# mcu.net
KiCad netlist of a schematic drawn in Altium Designer
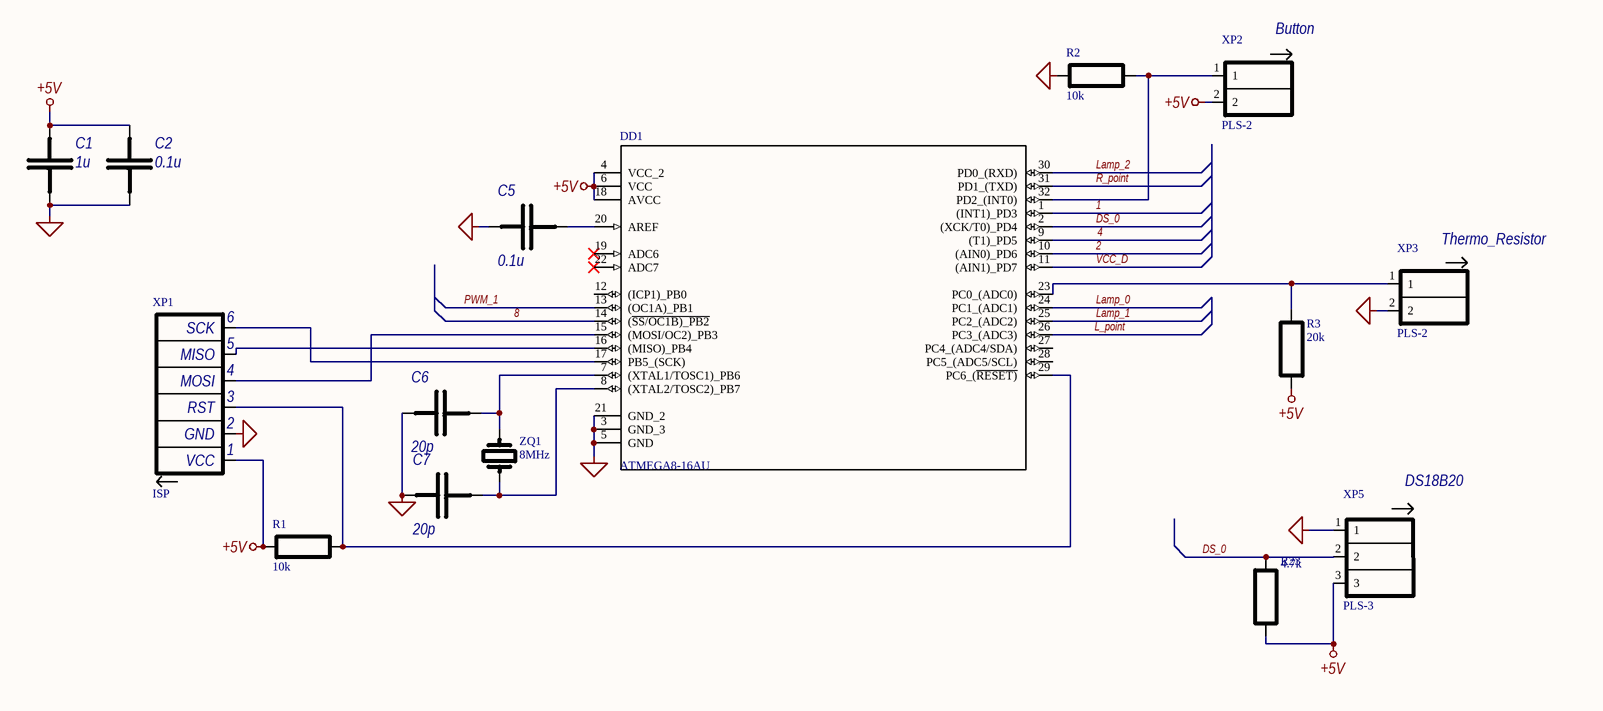
[diagram p0: mcu.SchDoc]

(export (version "E")
  (design (tool "Eeschema 10.0.6"))
  (components
    (comp (ref "C1")
      (value "1u")
      (footprint "CR2012-0805")
      (libsource (lib "sobol_lib") (part "C0805-1u-X7R"))
    )
    (comp (ref "C2")
      (value "0.1u")
      (footprint "CR2012-0805")
      (libsource (lib "sobol_lib") (part "C0805-0.1u-X7R"))
    )
    (comp (ref "C5")
      (value "0.1u")
      (footprint "CR2012-0805")
      (libsource (lib "sobol_lib") (part "C0805-0.1u-X7R"))
    )
    (comp (ref "C6")
      (value "20p")
      (footprint "CR2012-0805")
      (libsource (lib "sobol_lib") (part "C0805-20p-NPO"))
    )
    (comp (ref "C7")
      (value "20p")
      (footprint "CR2012-0805")
      (libsource (lib "sobol_lib") (part "C0805-20p-NPO"))
    )
    (comp (ref "DD1")
      (value "ATMEGA8-16AU")
      (footprint "*QFP80P900X900X120-32N")
      (description "AVR AVRВ® ATmega Microcontroller IC 8-Bit 16MHz 8KB _4K x 16_ FLASH 32-TQFP _7x7_")
      (fields (field (name "MF") "Microchip Technology"))
      (libsource (lib "sobol_lib") (part "ATMEGA8-16AU"))
    )
    (comp (ref "R1")
      (value "10k")
      (footprint "CR2012-0805")
      (libsource (lib "sobol_lib") (part "R0805-10k-5%"))
    )
    (comp (ref "R2")
      (value "10k")
      (footprint "CR2012-0805")
      (libsource (lib "sobol_lib") (part "R0805-10k-5%"))
    )
    (comp (ref "R3")
      (value "20k")
      (footprint "CR2012-0805")
      (libsource (lib "sobol_lib") (part "R0805-20k-5%"))
    )
    (comp (ref "R23")
      (value "4.7k")
      (footprint "CR2012-0805")
      (libsource (lib "sobol_lib") (part "R0805-4k7-5%"))
    )
    (comp (ref "XP1") (value "ISP") (footprint "PLS-6") (libsource (lib "sobol_lib") (part "ISP")))
    (comp (ref "XP2") (value "PLS-2") (footprint "PLS-2") (libsource (lib "sobol_lib") (part "PLS-2")))
    (comp (ref "XP3") (value "PLS-2") (footprint "PLS-2") (libsource (lib "sobol_lib") (part "PLS-2")))
    (comp (ref "XP5") (value "PLS-3") (footprint "PLS-3") (libsource (lib "sobol_lib") (part "PLS-3")))
    (comp (ref "ZQ1")
      (value "8MHz")
      (footprint "CRYSTAL")
      (libsource (lib "sobol_lib") (part "Crystal_8MHz"))
    )
  )
  (nets
    (net (code "1") (name "+5V") (class "Default")
      (node (ref "C1") (pin "1") (pinfunction "1_1") (pintype "passive"))
      (node (ref "C2") (pin "1") (pinfunction "1_1") (pintype "passive"))
      (node (ref "DD1") (pin "18") (pinfunction "AVCC_18") (pintype "power_in"))
      (node (ref "DD1") (pin "4") (pinfunction "VCC_2_4") (pintype "power_in"))
      (node (ref "DD1") (pin "6") (pinfunction "VCC_6") (pintype "power_in"))
      (node (ref "R1") (pin "1") (pinfunction "1_1") (pintype "passive"))
      (node (ref "R23") (pin "2") (pinfunction "2_2") (pintype "passive"))
      (node (ref "R3") (pin "1") (pinfunction "1_1") (pintype "passive"))
      (node (ref "XP1") (pin "1") (pinfunction "VCC_1") (pintype "passive"))
      (node (ref "XP2") (pin "2") (pinfunction "2_2") (pintype "passive"))
      (node (ref "XP5") (pin "3") (pinfunction "3_3") (pintype "passive"))
    )
    (net (code "2") (name "/1") (class "Default")
      (node (ref "DD1") (pin "1") (pinfunction "(INT1)_PD3_1") (pintype "bidirectional"))
    )
    (net (code "3") (name "/2") (class "Default")
      (node (ref "DD1") (pin "10") (pinfunction "(AIN0)_PD6_10") (pintype "bidirectional"))
    )
    (net (code "4") (name "/4") (class "Default")
      (node (ref "DD1") (pin "9") (pinfunction "(T1)_PD5_9") (pintype "bidirectional"))
    )
    (net (code "5") (name "/8") (class "Default")
      (node (ref "DD1") (pin "14") (pinfunction "(~{SS/OC1B)_PB2}_14") (pintype "bidirectional"))
    )
    (net (code "6") (name "/DS_0") (class "Default")
      (node (ref "DD1") (pin "2") (pinfunction "(XCK/T0)_PD4_2") (pintype "bidirectional"))
      (node (ref "R23") (pin "1") (pinfunction "1_1") (pintype "passive"))
      (node (ref "XP5") (pin "2") (pinfunction "2_2") (pintype "passive"))
    )
    (net (code "7") (name "/L_point") (class "Default")
      (node (ref "DD1") (pin "26") (pinfunction "PC3_(ADC3)_26") (pintype "bidirectional"))
    )
    (net (code "8") (name "/Lamp_0") (class "Default")
      (node (ref "DD1") (pin "24") (pinfunction "PC1_(ADC1)_24") (pintype "bidirectional"))
    )
    (net (code "9") (name "/Lamp_1") (class "Default")
      (node (ref "DD1") (pin "25") (pinfunction "PC2_(ADC2)_25") (pintype "bidirectional"))
    )
    (net (code "10") (name "/Lamp_2") (class "Default")
      (node (ref "DD1") (pin "30") (pinfunction "PD0_(RXD)_30") (pintype "bidirectional"))
    )
    (net (code "11") (name "/PWM_1") (class "Default")
      (node (ref "DD1") (pin "13") (pinfunction "(OC1A)_PB1_13") (pintype "bidirectional"))
    )
    (net (code "12") (name "/R_point") (class "Default")
      (node (ref "DD1") (pin "31") (pinfunction "PD1_(TXD)_31") (pintype "bidirectional"))
    )
    (net (code "13") (name "/VCC_D") (class "Default")
      (node (ref "DD1") (pin "11") (pinfunction "(AIN1)_PD7_11") (pintype "bidirectional"))
    )
    (net (code "14") (name "Net-(DD1-(MISO)_PB4)") (class "Default")
      (node (ref "DD1") (pin "16") (pinfunction "(MISO)_PB4_16") (pintype "bidirectional"))
      (node (ref "XP1") (pin "5") (pinfunction "MISO_5") (pintype "passive"))
    )
    (net (code "15") (name "Net-(DD1-(MOSI{slash}OC2)_PB3)") (class "Default")
      (node (ref "DD1") (pin "15") (pinfunction "(MOSI/OC2)_PB3_15") (pintype "bidirectional"))
      (node (ref "XP1") (pin "4") (pinfunction "MOSI_4") (pintype "passive"))
    )
    (net (code "16") (name "Net-(DD1-(XTAL1{slash}TOSC1)_PB6)") (class "Default")
      (node (ref "C6") (pin "2") (pinfunction "2_2") (pintype "passive"))
      (node (ref "DD1") (pin "7") (pinfunction "(XTAL1/TOSC1)_PB6_7") (pintype "bidirectional"))
      (node (ref "ZQ1") (pin "1") (pinfunction "1_1") (pintype "passive"))
    )
    (net (code "17") (name "Net-(DD1-(XTAL2{slash}TOSC2)_PB7)") (class "Default")
      (node (ref "C7") (pin "2") (pinfunction "2_2") (pintype "passive"))
      (node (ref "DD1") (pin "8") (pinfunction "(XTAL2/TOSC2)_PB7_8") (pintype "bidirectional"))
      (node (ref "ZQ1") (pin "2") (pinfunction "2_2") (pintype "passive"))
    )
    (net (code "18") (name "Net-(DD1-AREF)") (class "Default")
      (node (ref "C5") (pin "2") (pinfunction "2_2") (pintype "passive"))
      (node (ref "DD1") (pin "20") (pinfunction "AREF_20") (pintype "input"))
    )
    (net (code "19") (name "Net-(DD1-PB5_(SCK))") (class "Default")
      (node (ref "DD1") (pin "17") (pinfunction "PB5_(SCK)_17") (pintype "bidirectional"))
      (node (ref "XP1") (pin "6") (pinfunction "SCK_6") (pintype "passive"))
    )
    (net (code "20") (name "Net-(DD1-PC0_(ADC0))") (class "Default")
      (node (ref "DD1") (pin "23") (pinfunction "PC0_(ADC0)_23") (pintype "bidirectional"))
      (node (ref "R3") (pin "2") (pinfunction "2_2") (pintype "passive"))
      (node (ref "XP3") (pin "1") (pinfunction "1_1") (pintype "passive"))
    )
    (net (code "21") (name "Net-(DD1-PC6_(~{RESET)})") (class "Default")
      (node (ref "DD1") (pin "29") (pinfunction "PC6_(~{RESET)}_29") (pintype "bidirectional"))
      (node (ref "R1") (pin "2") (pinfunction "2_2") (pintype "passive"))
      (node (ref "XP1") (pin "3") (pinfunction "RST_3") (pintype "passive"))
    )
    (net (code "22") (name "Net-(DD1-PD2_(INT0))") (class "Default")
      (node (ref "DD1") (pin "32") (pinfunction "PD2_(INT0)_32") (pintype "bidirectional"))
      (node (ref "R2") (pin "2") (pinfunction "2_2") (pintype "passive"))
      (node (ref "XP2") (pin "1") (pinfunction "1_1") (pintype "passive"))
    )
    (net (code "23") (name "SGND") (class "Default")
      (node (ref "C1") (pin "2") (pinfunction "2_2") (pintype "passive"))
      (node (ref "C2") (pin "2") (pinfunction "2_2") (pintype "passive"))
      (node (ref "C5") (pin "1") (pinfunction "1_1") (pintype "passive"))
      (node (ref "C6") (pin "1") (pinfunction "1_1") (pintype "passive"))
      (node (ref "C7") (pin "1") (pinfunction "1_1") (pintype "passive"))
      (node (ref "DD1") (pin "21") (pinfunction "GND_2_21") (pintype "passive"))
      (node (ref "DD1") (pin "3") (pinfunction "GND_3_3") (pintype "passive"))
      (node (ref "DD1") (pin "5") (pinfunction "GND_5") (pintype "passive"))
      (node (ref "R2") (pin "1") (pinfunction "1_1") (pintype "passive"))
      (node (ref "XP1") (pin "2") (pinfunction "GND_2") (pintype "passive"))
      (node (ref "XP3") (pin "2") (pinfunction "2_2") (pintype "passive"))
      (node (ref "XP5") (pin "1") (pinfunction "1_1") (pintype "passive"))
    )
    (net (code "24") (name "unconnected-(DD1-(ICP1)_PB0-Pad12)") (class "Default")
      (node (ref "DD1") (pin "12") (pinfunction "(ICP1)_PB0_12") (pintype "bidirectional"))
    )
    (net (code "25") (name "unconnected-(DD1-ADC6-Pad19)") (class "Default")
      (node (ref "DD1") (pin "19") (pinfunction "ADC6_19") (pintype "input+no_connect"))
    )
    (net (code "26") (name "unconnected-(DD1-ADC7-Pad22)") (class "Default")
      (node (ref "DD1") (pin "22") (pinfunction "ADC7_22") (pintype "input+no_connect"))
    )
    (net (code "27") (name "unconnected-(DD1-PC4_(ADC4{slash}SDA)-Pad27)") (class "Default")
      (node (ref "DD1") (pin "27") (pinfunction "PC4_(ADC4/SDA)_27") (pintype "bidirectional"))
    )
    (net (code "28") (name "unconnected-(DD1-PC5_(ADC5{slash}SCL)-Pad28)") (class "Default")
      (node (ref "DD1") (pin "28") (pinfunction "PC5_(ADC5/SCL)_28") (pintype "bidirectional"))
    )
  )
)
